# Car.net
KiCad netlist of a schematic drawn in EAGLE
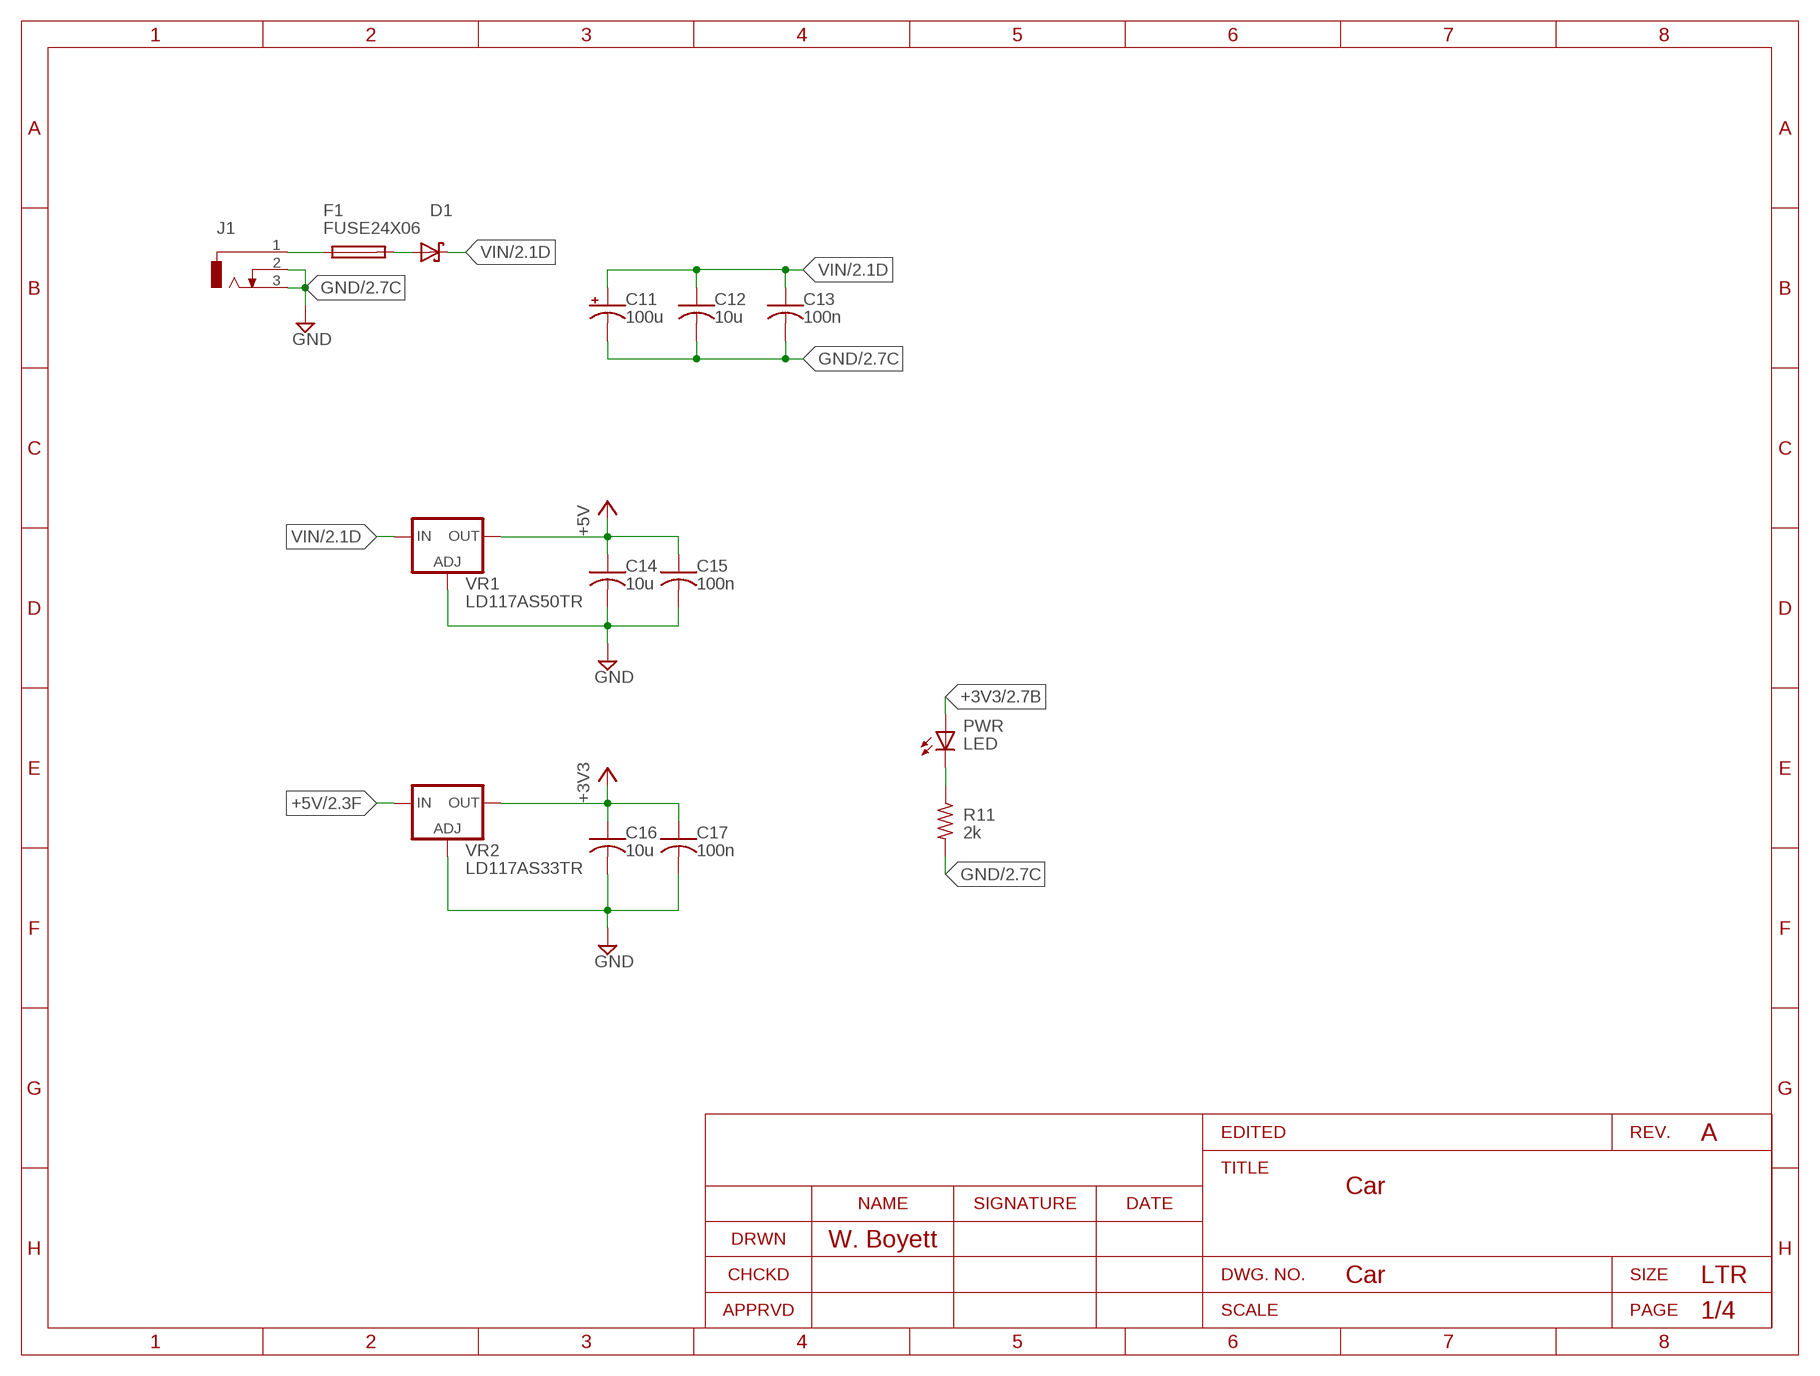
[diagram p0: schematic, sheet 1]
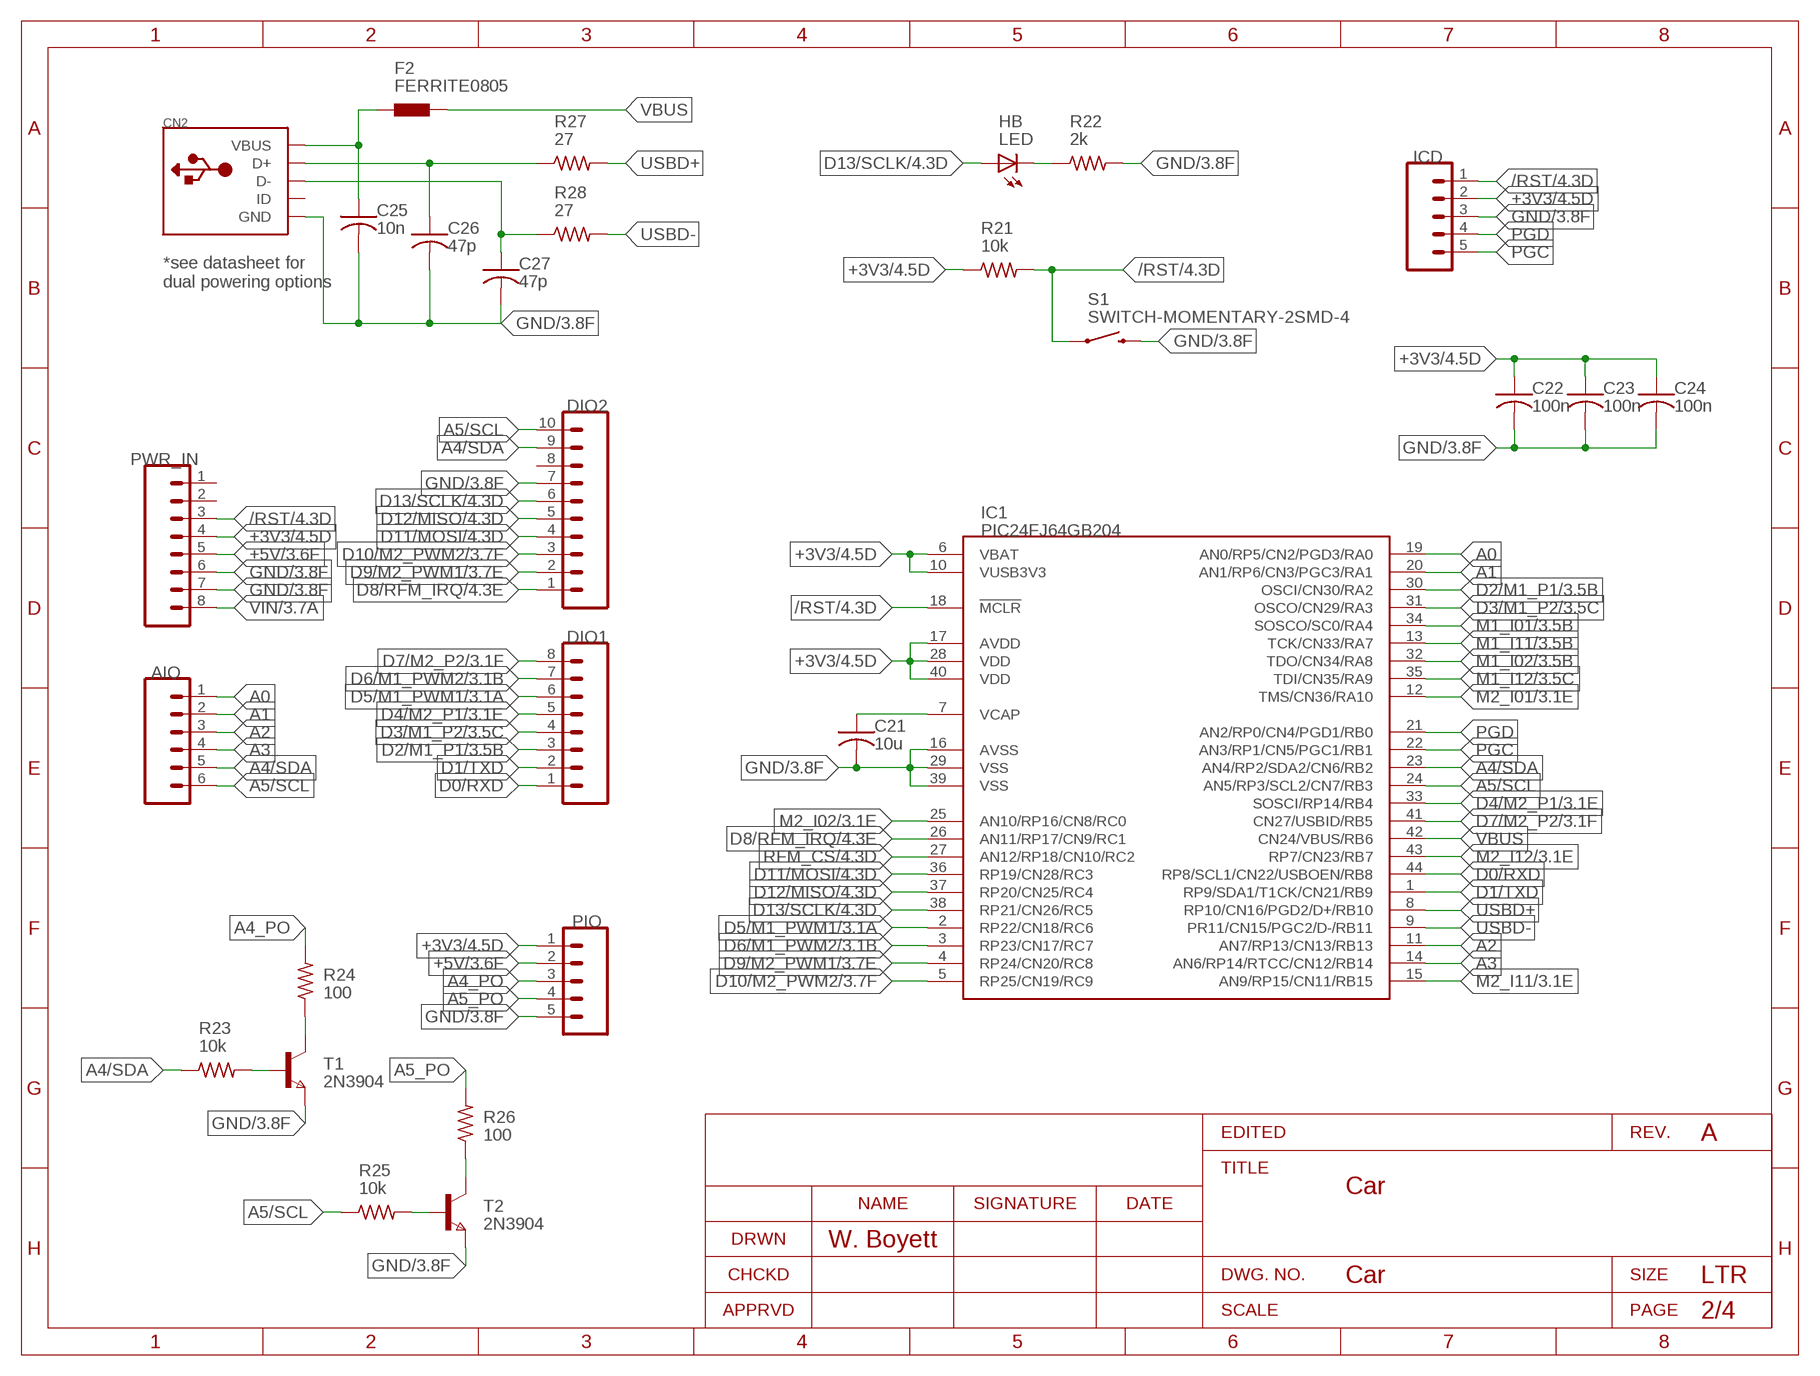
[diagram p1: schematic, sheet 2]
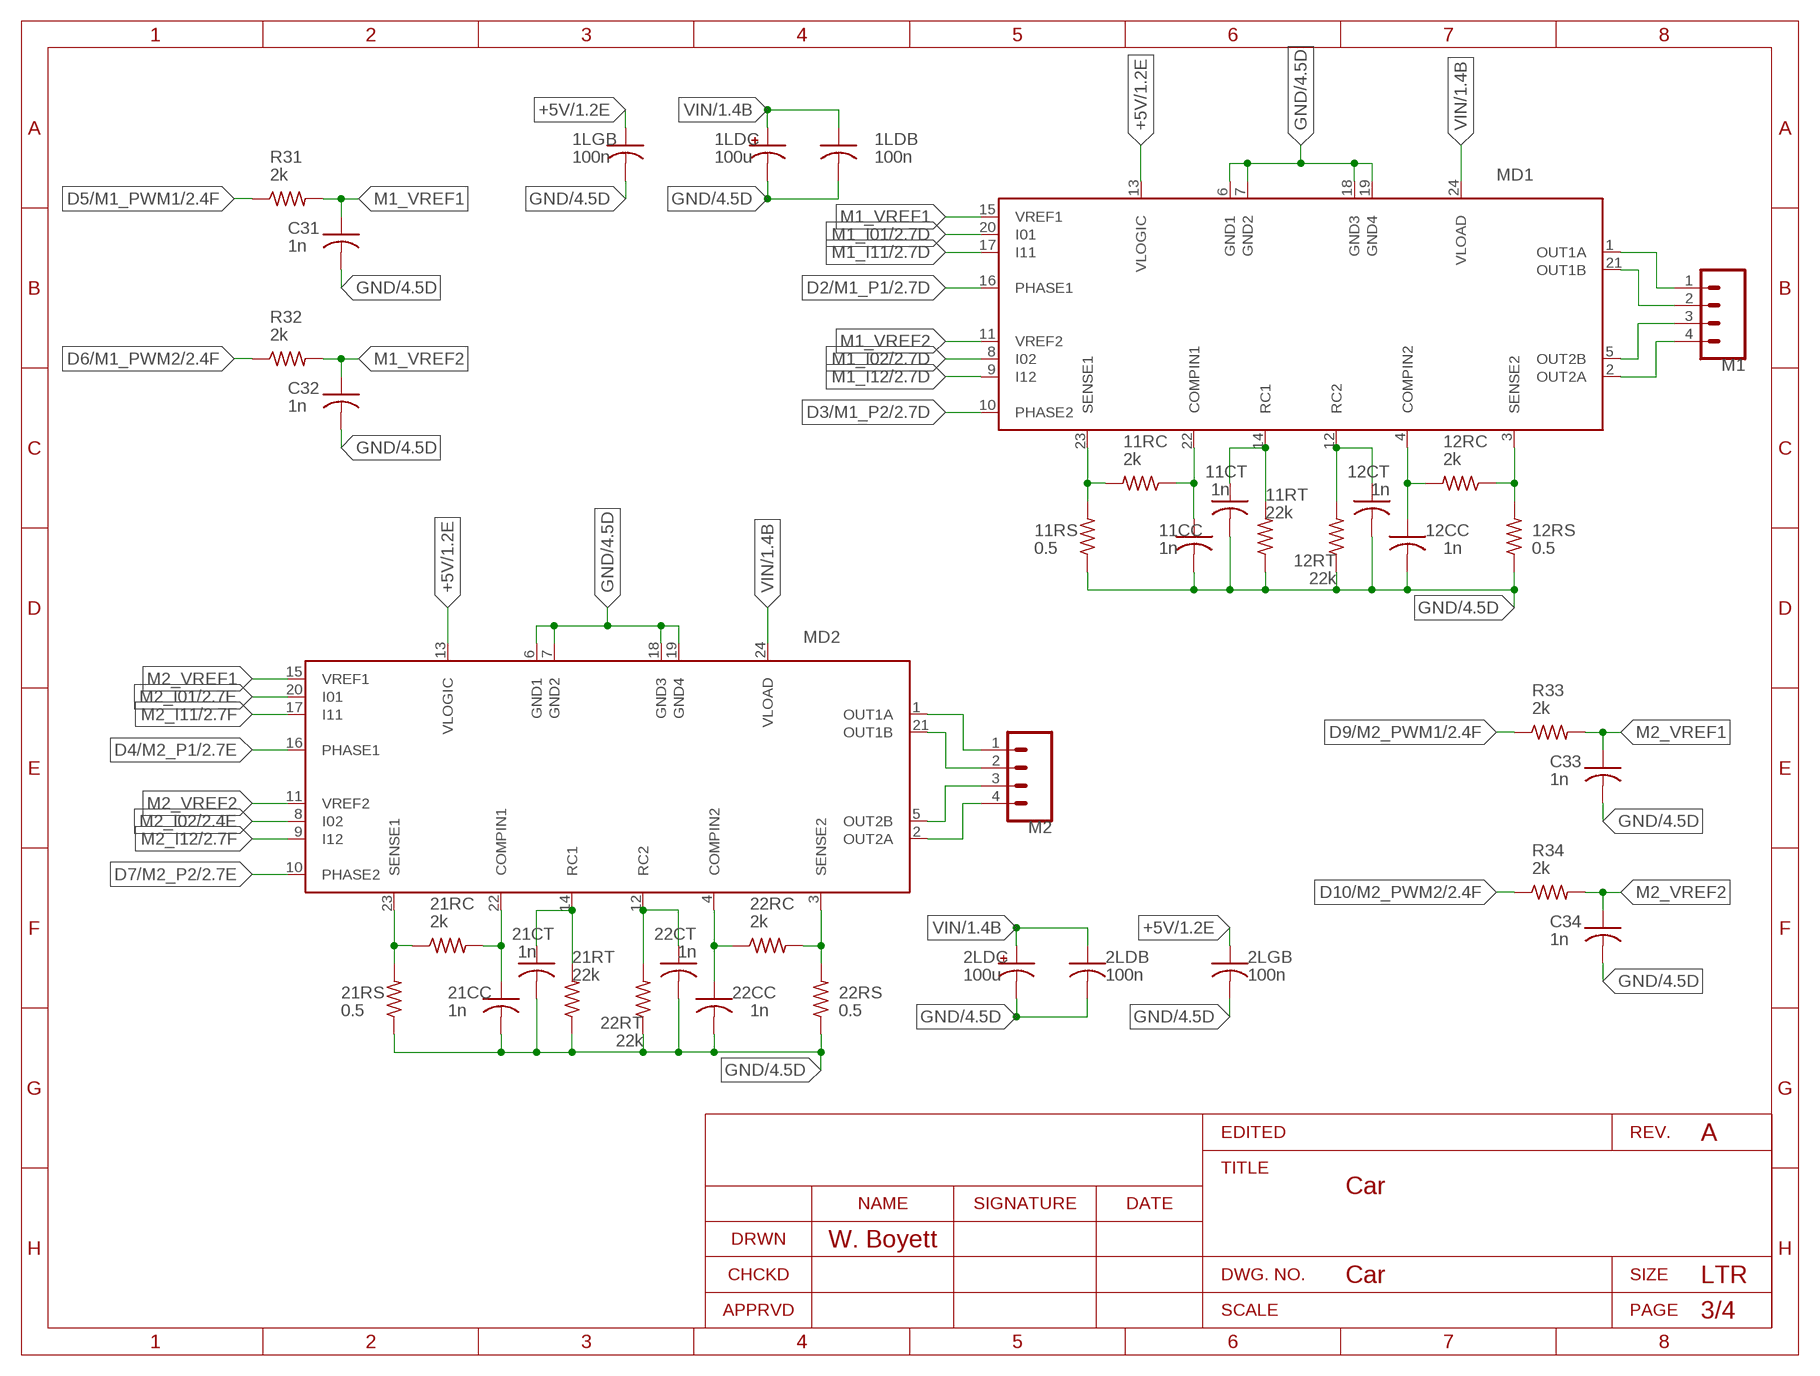
[diagram p2: schematic, sheet 3]
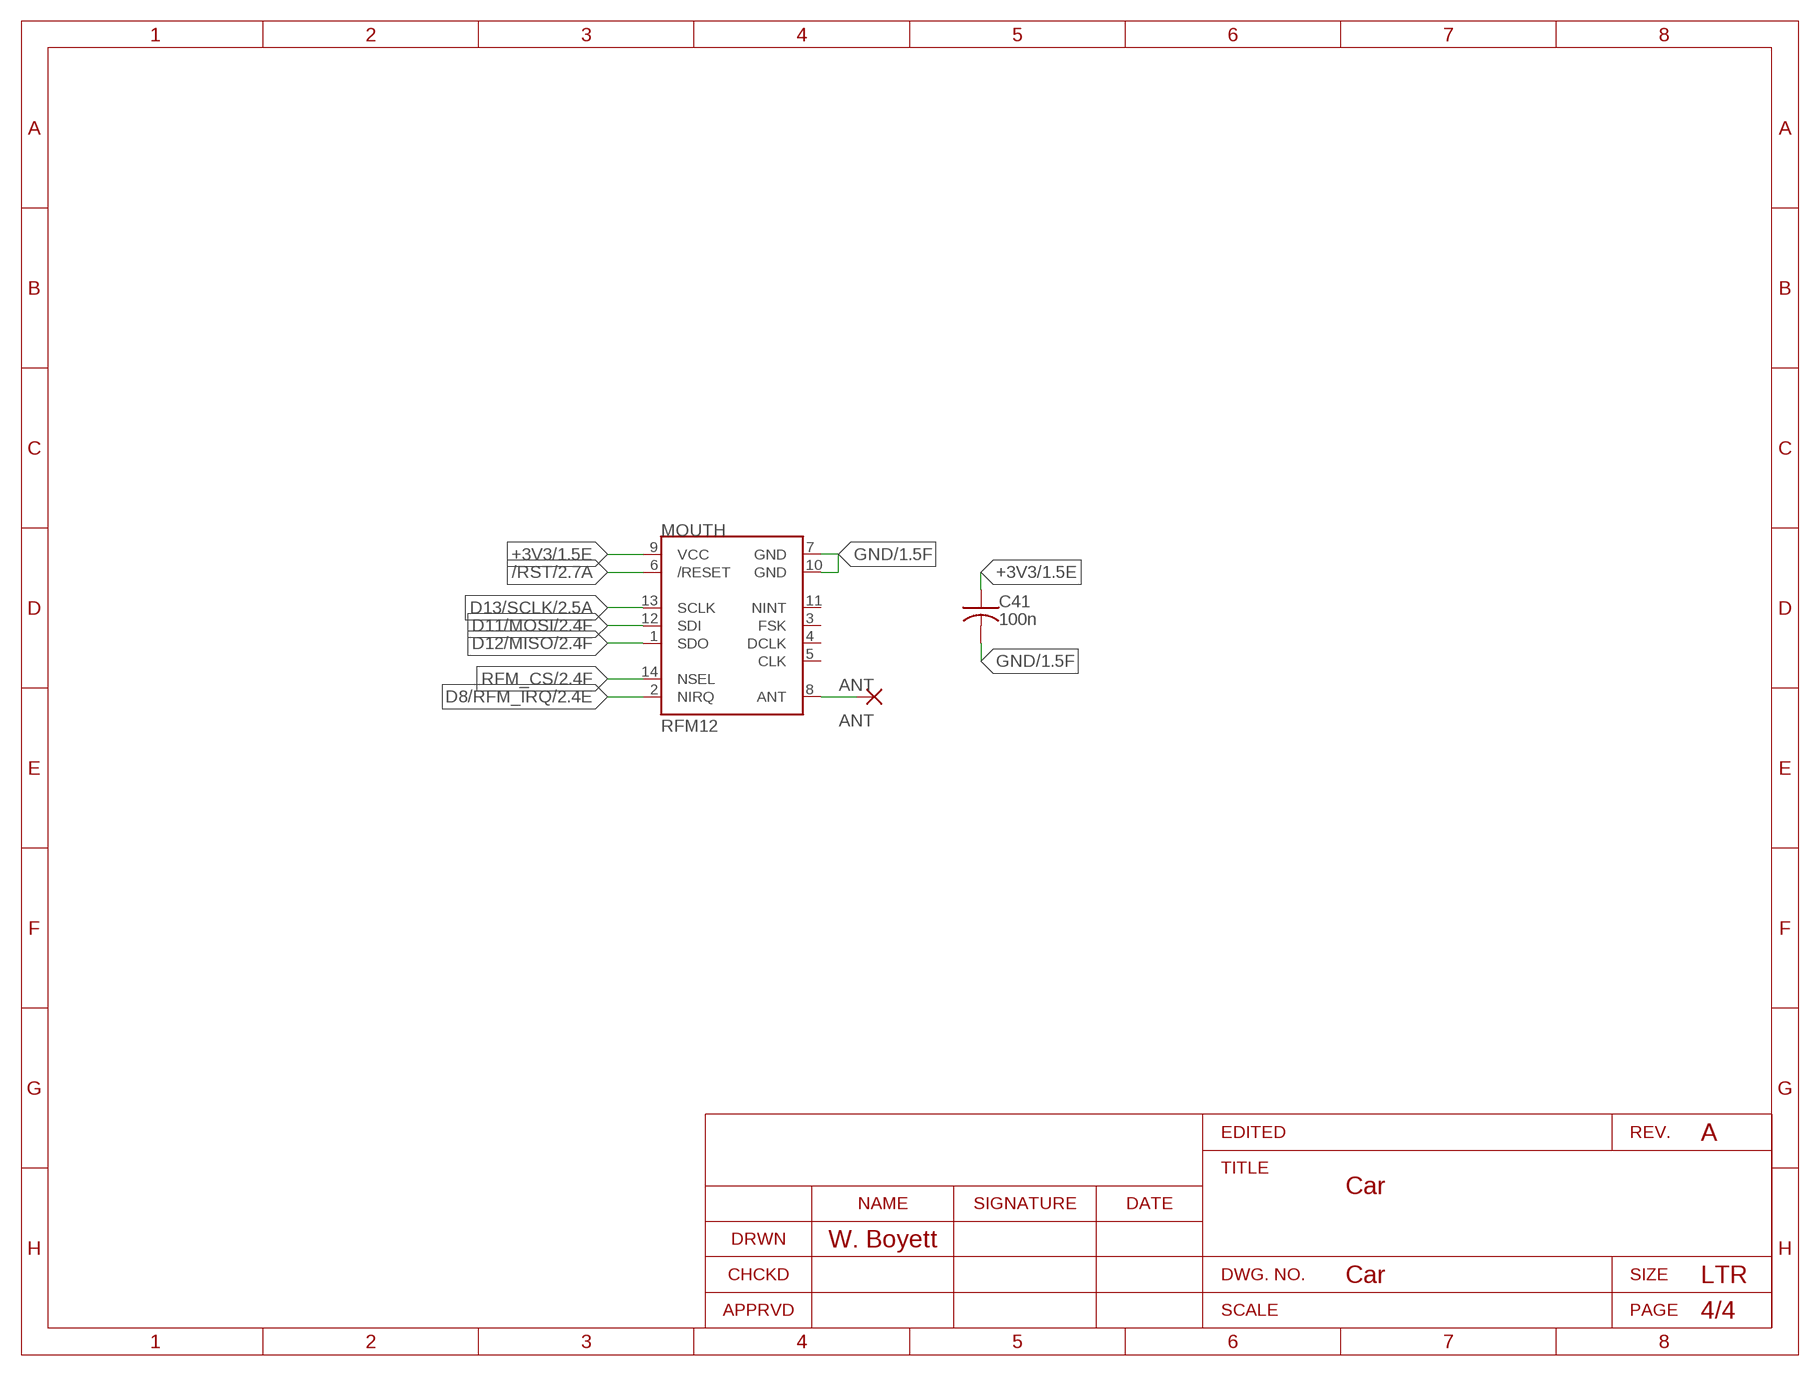
[diagram p3: schematic, sheet 4]

(export (version "E")
  (design (tool "Eeschema 10.0.6"))
  (components
    (comp (ref "C11")
      (value "100u")
      (footprint "eagle-import:PANASONIC_C")
      (libsource (lib "eagle-import") (part "CAP_POLC"))
    )
    (comp (ref "C12")
      (value "10u")
      (footprint "eagle-import:C1206")
      (libsource (lib "eagle-import") (part "C-USC1206"))
    )
    (comp (ref "C13")
      (value "100n")
      (footprint "eagle-import:C0805")
      (libsource (lib "eagle-import") (part "C-USC0805"))
    )
    (comp (ref "C14")
      (value "10u")
      (footprint "eagle-import:C1206")
      (libsource (lib "eagle-import") (part "C-USC1206"))
    )
    (comp (ref "C15")
      (value "100n")
      (footprint "eagle-import:C0805")
      (libsource (lib "eagle-import") (part "C-USC0805"))
    )
    (comp (ref "C16")
      (value "10u")
      (footprint "eagle-import:C1206")
      (libsource (lib "eagle-import") (part "C-USC1206"))
    )
    (comp (ref "C17")
      (value "100n")
      (footprint "eagle-import:C0805")
      (libsource (lib "eagle-import") (part "C-USC0805"))
    )
    (comp (ref "D1")
      (value "SCHOTTKY-DIODESMA")
      (footprint "eagle-import:SMA")
      (libsource (lib "eagle-import") (part "SCHOTTKY-DIODESMA"))
    )
    (comp (ref "F1")
      (value "FUSE24X06")
      (footprint "eagle-import:2SMD-24X06")
      (libsource (lib "eagle-import") (part "FUSE24X06"))
    )
    (comp (ref "J1")
      (value "DCJ0303")
      (footprint "eagle-import:DCJ0303")
      (libsource (lib "eagle-import") (part "DCJ0303"))
    )
    (comp (ref "PWR")
      (value "LED")
      (footprint "eagle-import:CHIP-LED0805")
      (libsource (lib "eagle-import") (part "LEDCHIP-LED0805"))
    )
    (comp (ref "R11")
      (value "2k")
      (footprint "eagle-import:R0805")
      (libsource (lib "eagle-import") (part "R-US_R0805"))
    )
    (comp (ref "VR1")
      (value "LD117AS50TR")
      (footprint "eagle-import:SOT223")
      (libsource (lib "eagle-import") (part "LD117A?S50TR"))
    )
    (comp (ref "VR2")
      (value "LD117AS33TR")
      (footprint "eagle-import:SOT223")
      (libsource (lib "eagle-import") (part "LD117A?S33TR"))
    )
    (comp (ref "1LDB")
      (value "100n")
      (footprint "eagle-import:C0805")
      (libsource (lib "eagle-import") (part "C-USC0805"))
    )
    (comp (ref "1LDC")
      (value "100u")
      (footprint "eagle-import:PANASONIC_C")
      (libsource (lib "eagle-import") (part "CAP_POLC"))
    )
    (comp (ref "1LGB")
      (value "100n")
      (footprint "eagle-import:C0805")
      (libsource (lib "eagle-import") (part "C-USC0805"))
    )
    (comp (ref "2LDB")
      (value "100n")
      (footprint "eagle-import:C0805")
      (libsource (lib "eagle-import") (part "C-USC0805"))
    )
    (comp (ref "2LDC")
      (value "100u")
      (footprint "eagle-import:PANASONIC_C")
      (libsource (lib "eagle-import") (part "CAP_POLC"))
    )
    (comp (ref "2LGB")
      (value "100n")
      (footprint "eagle-import:C0805")
      (libsource (lib "eagle-import") (part "C-USC0805"))
    )
    (comp (ref "11CC")
      (value "1n")
      (footprint "eagle-import:C0805")
      (libsource (lib "eagle-import") (part "C-USC0805"))
    )
    (comp (ref "11CT")
      (value "1n")
      (footprint "eagle-import:C0805")
      (libsource (lib "eagle-import") (part "C-USC0805"))
    )
    (comp (ref "11RC")
      (value "2k")
      (footprint "eagle-import:R0805")
      (libsource (lib "eagle-import") (part "R-US_R0805"))
    )
    (comp (ref "11RS")
      (value "0.5")
      (footprint "eagle-import:R1210")
      (libsource (lib "eagle-import") (part "resistor_R-US_R1210"))
    )
    (comp (ref "11RT")
      (value "22k")
      (footprint "eagle-import:R0805")
      (libsource (lib "eagle-import") (part "R-US_R0805"))
    )
    (comp (ref "12CC")
      (value "1n")
      (footprint "eagle-import:C0805")
      (libsource (lib "eagle-import") (part "C-USC0805"))
    )
    (comp (ref "12CT")
      (value "1n")
      (footprint "eagle-import:C0805")
      (libsource (lib "eagle-import") (part "C-USC0805"))
    )
    (comp (ref "12RC")
      (value "2k")
      (footprint "eagle-import:R0805")
      (libsource (lib "eagle-import") (part "R-US_R0805"))
    )
    (comp (ref "12RS")
      (value "0.5")
      (footprint "eagle-import:R1210")
      (libsource (lib "eagle-import") (part "resistor_R-US_R1210"))
    )
    (comp (ref "12RT")
      (value "22k")
      (footprint "eagle-import:R0805")
      (libsource (lib "eagle-import") (part "R-US_R0805"))
    )
    (comp (ref "21CC")
      (value "1n")
      (footprint "eagle-import:C0805")
      (libsource (lib "eagle-import") (part "C-USC0805"))
    )
    (comp (ref "21CT")
      (value "1n")
      (footprint "eagle-import:C0805")
      (libsource (lib "eagle-import") (part "C-USC0805"))
    )
    (comp (ref "21RC")
      (value "2k")
      (footprint "eagle-import:R0805")
      (libsource (lib "eagle-import") (part "R-US_R0805"))
    )
    (comp (ref "21RS")
      (value "0.5")
      (footprint "eagle-import:R1210")
      (libsource (lib "eagle-import") (part "resistor_R-US_R1210"))
    )
    (comp (ref "21RT")
      (value "22k")
      (footprint "eagle-import:R0805")
      (libsource (lib "eagle-import") (part "R-US_R0805"))
    )
    (comp (ref "22CC")
      (value "1n")
      (footprint "eagle-import:C0805")
      (libsource (lib "eagle-import") (part "C-USC0805"))
    )
    (comp (ref "22CT")
      (value "1n")
      (footprint "eagle-import:C0805")
      (libsource (lib "eagle-import") (part "C-USC0805"))
    )
    (comp (ref "22RC")
      (value "2k")
      (footprint "eagle-import:R0805")
      (libsource (lib "eagle-import") (part "R-US_R0805"))
    )
    (comp (ref "22RS")
      (value "0.5")
      (footprint "eagle-import:R1210")
      (libsource (lib "eagle-import") (part "resistor_R-US_R1210"))
    )
    (comp (ref "22RT")
      (value "22k")
      (footprint "eagle-import:R0805")
      (libsource (lib "eagle-import") (part "R-US_R0805"))
    )
    (comp (ref "C31")
      (value "1n")
      (footprint "eagle-import:C0805")
      (libsource (lib "eagle-import") (part "C-USC0805"))
    )
    (comp (ref "C32")
      (value "1n")
      (footprint "eagle-import:C0805")
      (libsource (lib "eagle-import") (part "C-USC0805"))
    )
    (comp (ref "C33")
      (value "1n")
      (footprint "eagle-import:C0805")
      (libsource (lib "eagle-import") (part "C-USC0805"))
    )
    (comp (ref "C34")
      (value "1n")
      (footprint "eagle-import:C0805")
      (libsource (lib "eagle-import") (part "C-USC0805"))
    )
    (comp (ref "M1")
      (value "M04LOCK")
      (footprint "eagle-import:1X04_LOCK")
      (libsource (lib "eagle-import") (part "M04LOCK"))
    )
    (comp (ref "M2")
      (value "M04LOCK")
      (footprint "eagle-import:1X04_LOCK")
      (libsource (lib "eagle-import") (part "M04LOCK"))
    )
    (comp (ref "MD1")
      (value "MTS62C19A")
      (footprint "eagle-import:SOP24L")
      (libsource (lib "eagle-import") (part "MTS62C19A"))
    )
    (comp (ref "MD2")
      (value "MTS62C19A")
      (footprint "eagle-import:SOP24L")
      (libsource (lib "eagle-import") (part "MTS62C19A"))
    )
    (comp (ref "R31")
      (value "2k")
      (footprint "eagle-import:R0805")
      (libsource (lib "eagle-import") (part "R-US_R0805"))
    )
    (comp (ref "R32")
      (value "2k")
      (footprint "eagle-import:R0805")
      (libsource (lib "eagle-import") (part "R-US_R0805"))
    )
    (comp (ref "R33")
      (value "2k")
      (footprint "eagle-import:R0805")
      (libsource (lib "eagle-import") (part "R-US_R0805"))
    )
    (comp (ref "R34")
      (value "2k")
      (footprint "eagle-import:R0805")
      (libsource (lib "eagle-import") (part "R-US_R0805"))
    )
    (comp (ref "AIO")
      (value "M06LOCK")
      (footprint "eagle-import:1X06_LOCK")
      (libsource (lib "eagle-import") (part "M06LOCK"))
    )
    (comp (ref "C21")
      (value "10u")
      (footprint "eagle-import:C1206")
      (libsource (lib "eagle-import") (part "C-USC1206"))
    )
    (comp (ref "C22")
      (value "100n")
      (footprint "eagle-import:C0805")
      (libsource (lib "eagle-import") (part "C-USC0805"))
    )
    (comp (ref "C23")
      (value "100n")
      (footprint "eagle-import:C0805")
      (libsource (lib "eagle-import") (part "C-USC0805"))
    )
    (comp (ref "C24")
      (value "100n")
      (footprint "eagle-import:C0805")
      (libsource (lib "eagle-import") (part "C-USC0805"))
    )
    (comp (ref "C25")
      (value "10n")
      (footprint "eagle-import:C0805")
      (fields (field (name "PN-DK") "399-1158-1-ND"))
      (libsource (lib "eagle-import") (part "C-USC0805"))
    )
    (comp (ref "C26")
      (value "47p")
      (footprint "eagle-import:C0805")
      (fields (field (name "PN-DK") "399-1117-1-ND"))
      (libsource (lib "eagle-import") (part "C-USC0805"))
    )
    (comp (ref "C27")
      (value "47p")
      (footprint "eagle-import:C0805")
      (fields (field (name "PN-DK") "399-1117-1-ND"))
      (libsource (lib "eagle-import") (part "C-USC0805"))
    )
    (comp (ref "CN2")
      (value "USBMINIB")
      (footprint "eagle-import:USB-MINIB")
      (libsource (lib "eagle-import") (part "USBMINIB"))
    )
    (comp (ref "DIO1")
      (value "M08LOCK")
      (footprint "eagle-import:1X08_LOCK")
      (libsource (lib "eagle-import") (part "M08LOCK"))
    )
    (comp (ref "DIO2")
      (value "M10LOCK")
      (footprint "eagle-import:1X10_LOCK")
      (libsource (lib "eagle-import") (part "M10LOCK"))
    )
    (comp (ref "F2")
      (value "FERRITE0805")
      (footprint "eagle-import:0805")
      (libsource (lib "eagle-import") (part "FERRITE0805"))
    )
    (comp (ref "HB")
      (value "LED")
      (footprint "eagle-import:CHIP-LED0805")
      (libsource (lib "eagle-import") (part "LEDCHIP-LED0805"))
    )
    (comp (ref "IC1")
      (value "PIC24FJ64GB204")
      (footprint "eagle-import:TQFP44")
      (fields (field (name "MPN") "PIC24FJ64GA004-E/PT"))
      (libsource (lib "eagle-import") (part "PIC24FJ64GB204"))
    )
    (comp (ref "ICD")
      (value "M05LOCK")
      (footprint "eagle-import:1X05_LOCK")
      (libsource (lib "eagle-import") (part "M05LOCK"))
    )
    (comp (ref "PIO")
      (value "M05LOCK")
      (footprint "eagle-import:1X05_LOCK")
      (libsource (lib "eagle-import") (part "M05LOCK"))
    )
    (comp (ref "PWR_IN")
      (value "M08LOCK")
      (footprint "eagle-import:1X08_LOCK")
      (libsource (lib "eagle-import") (part "M08LOCK"))
    )
    (comp (ref "R21")
      (value "10k")
      (footprint "eagle-import:R0805")
      (libsource (lib "eagle-import") (part "R-US_R0805"))
    )
    (comp (ref "R22")
      (value "2k")
      (footprint "eagle-import:R0805")
      (libsource (lib "eagle-import") (part "R-US_R0805"))
    )
    (comp (ref "R23")
      (value "10k")
      (footprint "eagle-import:R0805")
      (libsource (lib "eagle-import") (part "R-US_R0805"))
    )
    (comp (ref "R24")
      (value "100")
      (footprint "eagle-import:R0805")
      (libsource (lib "eagle-import") (part "R-US_R0805"))
    )
    (comp (ref "R25")
      (value "10k")
      (footprint "eagle-import:R0805")
      (libsource (lib "eagle-import") (part "R-US_R0805"))
    )
    (comp (ref "R26")
      (value "100")
      (footprint "eagle-import:R0805")
      (libsource (lib "eagle-import") (part "R-US_R0805"))
    )
    (comp (ref "R27")
      (value "27")
      (footprint "eagle-import:R0805")
      (libsource (lib "eagle-import") (part "resistor_R-US_R0805"))
    )
    (comp (ref "R28")
      (value "27")
      (footprint "eagle-import:R0805")
      (libsource (lib "eagle-import") (part "resistor_R-US_R0805"))
    )
    (comp (ref "S1")
      (value "SWITCH-MOMENTARY-2SMD-4")
      (footprint "eagle-import:TACTILE_SWITCH_TALL")
      (libsource (lib "eagle-import") (part "SWITCH-MOMENTARY-2SMD-4"))
    )
    (comp (ref "T1")
      (value "2N3904")
      (footprint "eagle-import:SOT-23")
      (fields (field (name "MPN") "DSS20201L-7"))
      (libsource (lib "eagle-import") (part "NPNSOT23"))
    )
    (comp (ref "T2")
      (value "2N3904")
      (footprint "eagle-import:SOT-23")
      (fields (field (name "MPN") "DSS20201L-7"))
      (libsource (lib "eagle-import") (part "NPNSOT23"))
    )
    (comp (ref "ANT")
      (value "ANT")
      (footprint "eagle-import:2,15_1,0")
      (libsource (lib "eagle-import") (part "2,15/1,0"))
    )
    (comp (ref "C41")
      (value "100n")
      (footprint "eagle-import:C0805")
      (libsource (lib "eagle-import") (part "C-USC0805"))
    )
    (comp (ref "MOUTH")
      (value "RFM12")
      (footprint "eagle-import:RFM12-XXX-S2")
      (libsource (lib "eagle-import") (part "RFM12"))
    )
  )
  (nets
    (net (code "1") (name "+3V3") (class "Default")
      (node (ref "C16") (pin "1") (pinfunction "1_1") (pintype "passive"))
      (node (ref "C17") (pin "1") (pinfunction "1_1") (pintype "passive"))
      (node (ref "C22") (pin "1") (pinfunction "1_1") (pintype "passive"))
      (node (ref "C23") (pin "1") (pinfunction "1_1") (pintype "passive"))
      (node (ref "C24") (pin "1") (pinfunction "1_1") (pintype "passive"))
      (node (ref "C41") (pin "1") (pinfunction "1_1") (pintype "passive"))
      (node (ref "IC1") (pin "10") (pinfunction "VUSB3V3_10") (pintype "bidirectional"))
      (node (ref "IC1") (pin "17") (pinfunction "AVDD_17") (pintype "power_in"))
      (node (ref "IC1") (pin "28") (pinfunction "VDD_28") (pintype "power_in"))
      (node (ref "IC1") (pin "40") (pinfunction "VDD_40") (pintype "power_in"))
      (node (ref "IC1") (pin "6") (pinfunction "VBAT_6") (pintype "passive"))
      (node (ref "ICD") (pin "2") (pinfunction "2_2") (pintype "passive"))
      (node (ref "MOUTH") (pin "9") (pinfunction "VCC_9") (pintype "bidirectional"))
      (node (ref "PIO") (pin "1") (pinfunction "1_1") (pintype "passive"))
      (node (ref "PWR") (pin "A") (pinfunction "A_A") (pintype "passive"))
      (node (ref "PWR_IN") (pin "4") (pinfunction "4_4") (pintype "passive"))
      (node (ref "R21") (pin "1") (pinfunction "1_1") (pintype "passive"))
      (node (ref "VR2") (pin "2") (pinfunction "OUT_2") (pintype "passive"))
      (node (ref "VR2") (pin "4") (pinfunction "OUT_4") (pintype "passive"))
    )
    (net (code "2") (name "+5V") (class "Default")
      (node (ref "1LGB") (pin "1") (pinfunction "1_1") (pintype "passive"))
      (node (ref "2LGB") (pin "1") (pinfunction "1_1") (pintype "passive"))
      (node (ref "C14") (pin "1") (pinfunction "1_1") (pintype "passive"))
      (node (ref "C15") (pin "1") (pinfunction "1_1") (pintype "passive"))
      (node (ref "MD1") (pin "13") (pinfunction "VLOGIC_13") (pintype "bidirectional"))
      (node (ref "MD2") (pin "13") (pinfunction "VLOGIC_13") (pintype "bidirectional"))
      (node (ref "PIO") (pin "2") (pinfunction "2_2") (pintype "passive"))
      (node (ref "PWR_IN") (pin "5") (pinfunction "5_5") (pintype "passive"))
      (node (ref "VR1") (pin "2") (pinfunction "OUT_2") (pintype "passive"))
      (node (ref "VR1") (pin "4") (pinfunction "OUT_4") (pintype "passive"))
      (node (ref "VR2") (pin "3") (pinfunction "IN_3") (pintype "input"))
    )
    (net (code "3") (name "A0") (class "Default")
      (node (ref "AIO") (pin "1") (pinfunction "1_1") (pintype "passive"))
      (node (ref "IC1") (pin "19") (pinfunction "AN0/RP5/CN2/PGD3/RA0_19") (pintype "bidirectional"))
    )
    (net (code "4") (name "A1") (class "Default")
      (node (ref "AIO") (pin "2") (pinfunction "2_2") (pintype "passive"))
      (node (ref "IC1") (pin "20") (pinfunction "AN1/RP6/CN3/PGC3/RA1_20") (pintype "bidirectional"))
    )
    (net (code "5") (name "A2") (class "Default")
      (node (ref "AIO") (pin "3") (pinfunction "3_3") (pintype "passive"))
      (node (ref "IC1") (pin "11") (pinfunction "AN7/RP13/CN13/RB13_11") (pintype "bidirectional"))
    )
    (net (code "6") (name "A3") (class "Default")
      (node (ref "AIO") (pin "4") (pinfunction "4_4") (pintype "passive"))
      (node (ref "IC1") (pin "14") (pinfunction "AN6/RP14/RTCC/CN12/RB14_14") (pintype "bidirectional"))
    )
    (net (code "7") (name "A4_PO") (class "Default")
      (node (ref "PIO") (pin "3") (pinfunction "3_3") (pintype "passive"))
      (node (ref "R24") (pin "2") (pinfunction "2_2") (pintype "passive"))
    )
    (net (code "8") (name "A4{slash}SDA") (class "Default")
      (node (ref "AIO") (pin "5") (pinfunction "5_5") (pintype "passive"))
      (node (ref "DIO2") (pin "9") (pinfunction "9_9") (pintype "passive"))
      (node (ref "IC1") (pin "23") (pinfunction "AN4/RP2/SDA2/CN6/RB2_23") (pintype "bidirectional"))
      (node (ref "R23") (pin "1") (pinfunction "1_1") (pintype "passive"))
    )
    (net (code "9") (name "A5_PO") (class "Default")
      (node (ref "PIO") (pin "4") (pinfunction "4_4") (pintype "passive"))
      (node (ref "R26") (pin "2") (pinfunction "2_2") (pintype "passive"))
    )
    (net (code "10") (name "A5{slash}SCL") (class "Default")
      (node (ref "AIO") (pin "6") (pinfunction "6_6") (pintype "passive"))
      (node (ref "DIO2") (pin "10") (pinfunction "10_10") (pintype "passive"))
      (node (ref "IC1") (pin "24") (pinfunction "AN5/RP3/SCL2/CN7/RB3_24") (pintype "bidirectional"))
      (node (ref "R25") (pin "1") (pinfunction "1_1") (pintype "passive"))
    )
    (net (code "11") (name "D0{slash}RXD") (class "Default")
      (node (ref "DIO1") (pin "1") (pinfunction "1_1") (pintype "passive"))
      (node (ref "IC1") (pin "44") (pinfunction "RP8/SCL1/CN22/USBOEN/RB8_44") (pintype "bidirectional"))
    )
    (net (code "12") (name "D1{slash}TXD") (class "Default")
      (node (ref "DIO1") (pin "2") (pinfunction "2_2") (pintype "passive"))
      (node (ref "IC1") (pin "1") (pinfunction "RP9/SDA1/T1CK/CN21/RB9_1") (pintype "bidirectional"))
    )
    (net (code "13") (name "D2{slash}M1_P1") (class "Default")
      (node (ref "DIO1") (pin "3") (pinfunction "3_3") (pintype "passive"))
      (node (ref "IC1") (pin "30") (pinfunction "OSCI/CN30/RA2_30") (pintype "bidirectional"))
      (node (ref "MD1") (pin "16") (pinfunction "PHASE1_16") (pintype "bidirectional"))
    )
    (net (code "14") (name "D3{slash}M1_P2") (class "Default")
      (node (ref "DIO1") (pin "4") (pinfunction "4_4") (pintype "passive"))
      (node (ref "IC1") (pin "31") (pinfunction "OSCO/CN29/RA3_31") (pintype "bidirectional"))
      (node (ref "MD1") (pin "10") (pinfunction "PHASE2_10") (pintype "bidirectional"))
    )
    (net (code "15") (name "D4{slash}M2_P1") (class "Default")
      (node (ref "DIO1") (pin "5") (pinfunction "5_5") (pintype "passive"))
      (node (ref "IC1") (pin "33") (pinfunction "SOSCI/RP14/RB4_33") (pintype "bidirectional"))
      (node (ref "MD2") (pin "16") (pinfunction "PHASE1_16") (pintype "bidirectional"))
    )
    (net (code "16") (name "D5{slash}M1_PWM1") (class "Default")
      (node (ref "DIO1") (pin "6") (pinfunction "6_6") (pintype "passive"))
      (node (ref "IC1") (pin "2") (pinfunction "RP22/CN18/RC6_2") (pintype "bidirectional"))
      (node (ref "R31") (pin "1") (pinfunction "1_1") (pintype "passive"))
    )
    (net (code "17") (name "D6{slash}M1_PWM2") (class "Default")
      (node (ref "DIO1") (pin "7") (pinfunction "7_7") (pintype "passive"))
      (node (ref "IC1") (pin "3") (pinfunction "RP23/CN17/RC7_3") (pintype "bidirectional"))
      (node (ref "R32") (pin "1") (pinfunction "1_1") (pintype "passive"))
    )
    (net (code "18") (name "D7{slash}M2_P2") (class "Default")
      (node (ref "DIO1") (pin "8") (pinfunction "8_8") (pintype "passive"))
      (node (ref "IC1") (pin "41") (pinfunction "CN27/USBID/RB5_41") (pintype "bidirectional"))
      (node (ref "MD2") (pin "10") (pinfunction "PHASE2_10") (pintype "bidirectional"))
    )
    (net (code "19") (name "D8{slash}RFM_IRQ") (class "Default")
      (node (ref "DIO2") (pin "1") (pinfunction "1_1") (pintype "passive"))
      (node (ref "IC1") (pin "26") (pinfunction "AN11/RP17/CN9/RC1_26") (pintype "bidirectional"))
      (node (ref "MOUTH") (pin "2") (pinfunction "NIRQ_2") (pintype "output"))
    )
    (net (code "20") (name "D9{slash}M2_PWM1") (class "Default")
      (node (ref "DIO2") (pin "2") (pinfunction "2_2") (pintype "passive"))
      (node (ref "IC1") (pin "4") (pinfunction "RP24/CN20/RC8_4") (pintype "bidirectional"))
      (node (ref "R33") (pin "1") (pinfunction "1_1") (pintype "passive"))
    )
    (net (code "21") (name "D10{slash}M2_PWM2") (class "Default")
      (node (ref "DIO2") (pin "3") (pinfunction "3_3") (pintype "passive"))
      (node (ref "IC1") (pin "5") (pinfunction "RP25/CN19/RC9_5") (pintype "bidirectional"))
      (node (ref "R34") (pin "1") (pinfunction "1_1") (pintype "passive"))
    )
    (net (code "22") (name "D11{slash}MOSI") (class "Default")
      (node (ref "DIO2") (pin "4") (pinfunction "4_4") (pintype "passive"))
      (node (ref "IC1") (pin "36") (pinfunction "RP19/CN28/RC3_36") (pintype "bidirectional"))
      (node (ref "MOUTH") (pin "12") (pinfunction "SDI_12") (pintype "input"))
    )
    (net (code "23") (name "D12{slash}MISO") (class "Default")
      (node (ref "DIO2") (pin "5") (pinfunction "5_5") (pintype "passive"))
      (node (ref "IC1") (pin "37") (pinfunction "RP20/CN25/RC4_37") (pintype "bidirectional"))
      (node (ref "MOUTH") (pin "1") (pinfunction "SDO_1") (pintype "output"))
    )
    (net (code "24") (name "D13{slash}SCLK") (class "Default")
      (node (ref "DIO2") (pin "6") (pinfunction "6_6") (pintype "passive"))
      (node (ref "HB") (pin "A") (pinfunction "A_A") (pintype "passive"))
      (node (ref "IC1") (pin "38") (pinfunction "RP21/CN26/RC5_38") (pintype "bidirectional"))
      (node (ref "MOUTH") (pin "13") (pinfunction "SCLK_13") (pintype "input"))
    )
    (net (code "25") (name "GND") (class "Default")
      (node (ref "11CC") (pin "2") (pinfunction "2_2") (pintype "passive"))
      (node (ref "11CT") (pin "2") (pinfunction "2_2") (pintype "passive"))
      (node (ref "11RS") (pin "1") (pinfunction "1_1") (pintype "passive"))
      (node (ref "11RT") (pin "1") (pinfunction "1_1") (pintype "passive"))
      (node (ref "12CC") (pin "2") (pinfunction "2_2") (pintype "passive"))
      (node (ref "12CT") (pin "2") (pinfunction "2_2") (pintype "passive"))
      (node (ref "12RS") (pin "1") (pinfunction "1_1") (pintype "passive"))
      (node (ref "12RT") (pin "1") (pinfunction "1_1") (pintype "passive"))
      (node (ref "1LDB") (pin "2") (pinfunction "2_2") (pintype "passive"))
      (node (ref "1LDC") (pin "-") (pinfunction "-_-") (pintype "passive"))
      (node (ref "1LGB") (pin "2") (pinfunction "2_2") (pintype "passive"))
      (node (ref "21CC") (pin "2") (pinfunction "2_2") (pintype "passive"))
      (node (ref "21CT") (pin "2") (pinfunction "2_2") (pintype "passive"))
      (node (ref "21RS") (pin "1") (pinfunction "1_1") (pintype "passive"))
      (node (ref "21RT") (pin "1") (pinfunction "1_1") (pintype "passive"))
      (node (ref "22CC") (pin "2") (pinfunction "2_2") (pintype "passive"))
      (node (ref "22CT") (pin "2") (pinfunction "2_2") (pintype "passive"))
      (node (ref "22RS") (pin "1") (pinfunction "1_1") (pintype "passive"))
      (node (ref "22RT") (pin "1") (pinfunction "1_1") (pintype "passive"))
      (node (ref "2LDB") (pin "2") (pinfunction "2_2") (pintype "passive"))
      (node (ref "2LDC") (pin "-") (pinfunction "-_-") (pintype "passive"))
      (node (ref "2LGB") (pin "2") (pinfunction "2_2") (pintype "passive"))
      (node (ref "C11") (pin "-") (pinfunction "-_-") (pintype "passive"))
      (node (ref "C12") (pin "2") (pinfunction "2_2") (pintype "passive"))
      (node (ref "C13") (pin "2") (pinfunction "2_2") (pintype "passive"))
      (node (ref "C14") (pin "2") (pinfunction "2_2") (pintype "passive"))
      (node (ref "C15") (pin "2") (pinfunction "2_2") (pintype "passive"))
      (node (ref "C16") (pin "2") (pinfunction "2_2") (pintype "passive"))
      (node (ref "C17") (pin "2") (pinfunction "2_2") (pintype "passive"))
      (node (ref "C21") (pin "2") (pinfunction "2_2") (pintype "passive"))
      (node (ref "C22") (pin "2") (pinfunction "2_2") (pintype "passive"))
      (node (ref "C23") (pin "2") (pinfunction "2_2") (pintype "passive"))
      (node (ref "C24") (pin "2") (pinfunction "2_2") (pintype "passive"))
      (node (ref "C25") (pin "2") (pinfunction "2_2") (pintype "passive"))
      (node (ref "C26") (pin "2") (pinfunction "2_2") (pintype "passive"))
      (node (ref "C27") (pin "2") (pinfunction "2_2") (pintype "passive"))
      (node (ref "C31") (pin "2") (pinfunction "2_2") (pintype "passive"))
      (node (ref "C32") (pin "2") (pinfunction "2_2") (pintype "passive"))
      (node (ref "C33") (pin "2") (pinfunction "2_2") (pintype "passive"))
      (node (ref "C34") (pin "2") (pinfunction "2_2") (pintype "passive"))
      (node (ref "C41") (pin "2") (pinfunction "2_2") (pintype "passive"))
      (node (ref "CN2") (pin "GND") (pinfunction "GND_GND") (pintype "power_in"))
      (node (ref "DIO2") (pin "7") (pinfunction "7_7") (pintype "passive"))
      (node (ref "IC1") (pin "16") (pinfunction "AVSS_16") (pintype "power_in"))
      (node (ref "IC1") (pin "29") (pinfunction "VSS_29") (pintype "power_in"))
      (node (ref "IC1") (pin "39") (pinfunction "VSS_39") (pintype "power_in"))
      (node (ref "ICD") (pin "3") (pinfunction "3_3") (pintype "passive"))
      (node (ref "J1") (pin "2") (pinfunction "2_2") (pintype "passive"))
      (node (ref "J1") (pin "3") (pinfunction "3_3") (pintype "passive"))
      (node (ref "MD1") (pin "18") (pinfunction "GND3_18") (pintype "bidirectional"))
      (node (ref "MD1") (pin "19") (pinfunction "GND4_19") (pintype "bidirectional"))
      (node (ref "MD1") (pin "6") (pinfunction "GND1_6") (pintype "bidirectional"))
      (node (ref "MD1") (pin "7") (pinfunction "GND2_7") (pintype "bidirectional"))
      (node (ref "MD2") (pin "18") (pinfunction "GND3_18") (pintype "bidirectional"))
      (node (ref "MD2") (pin "19") (pinfunction "GND4_19") (pintype "bidirectional"))
      (node (ref "MD2") (pin "6") (pinfunction "GND1_6") (pintype "bidirectional"))
      (node (ref "MD2") (pin "7") (pinfunction "GND2_7") (pintype "bidirectional"))
      (node (ref "MOUTH") (pin "10") (pinfunction "GND_10") (pintype "bidirectional"))
      (node (ref "MOUTH") (pin "7") (pinfunction "GND_7") (pintype "bidirectional"))
      (node (ref "PIO") (pin "5") (pinfunction "5_5") (pintype "passive"))
      (node (ref "PWR_IN") (pin "6") (pinfunction "6_6") (pintype "passive"))
      (node (ref "PWR_IN") (pin "7") (pinfunction "7_7") (pintype "passive"))
      (node (ref "R11") (pin "2") (pinfunction "2_2") (pintype "passive"))
      (node (ref "R22") (pin "2") (pinfunction "2_2") (pintype "passive"))
      (node (ref "S1") (pin "B2") (pinfunction "2_B2") (pintype "passive"))
      (node (ref "T1") (pin "2") (pinfunction "E_2") (pintype "passive"))
      (node (ref "T2") (pin "2") (pinfunction "E_2") (pintype "passive"))
      (node (ref "VR1") (pin "1") (pinfunction "ADJ_1") (pintype "input"))
      (node (ref "VR2") (pin "1") (pinfunction "ADJ_1") (pintype "input"))
    )
    (net (code "26") (name "M1_I01") (class "Default")
      (node (ref "IC1") (pin "34") (pinfunction "SOSCO/SC0/RA4_34") (pintype "bidirectional"))
      (node (ref "MD1") (pin "20") (pinfunction "I01_20") (pintype "bidirectional"))
    )
    (net (code "27") (name "M1_I02") (class "Default")
      (node (ref "IC1") (pin "32") (pinfunction "TDO/CN34/RA8_32") (pintype "output"))
      (node (ref "MD1") (pin "8") (pinfunction "I02_8") (pintype "bidirectional"))
    )
    (net (code "28") (name "M1_I11") (class "Default")
      (node (ref "IC1") (pin "13") (pinfunction "TCK/CN33/RA7_13") (pintype "input"))
      (node (ref "MD1") (pin "17") (pinfunction "I11_17") (pintype "bidirectional"))
    )
    (net (code "29") (name "M1_I12") (class "Default")
      (node (ref "IC1") (pin "35") (pinfunction "TDI/CN35/RA9_35") (pintype "input"))
      (node (ref "MD1") (pin "9") (pinfunction "I12_9") (pintype "bidirectional"))
    )
    (net (code "30") (name "M1_VREF1") (class "Default")
      (node (ref "C31") (pin "1") (pinfunction "1_1") (pintype "passive"))
      (node (ref "MD1") (pin "15") (pinfunction "VREF1_15") (pintype "bidirectional"))
      (node (ref "R31") (pin "2") (pinfunction "2_2") (pintype "passive"))
    )
    (net (code "31") (name "M1_VREF2") (class "Default")
      (node (ref "C32") (pin "1") (pinfunction "1_1") (pintype "passive"))
      (node (ref "MD1") (pin "11") (pinfunction "VREF2_11") (pintype "bidirectional"))
      (node (ref "R32") (pin "2") (pinfunction "2_2") (pintype "passive"))
    )
    (net (code "32") (name "M2_I01") (class "Default")
      (node (ref "IC1") (pin "12") (pinfunction "TMS/CN36/RA10_12") (pintype "input"))
      (node (ref "MD2") (pin "20") (pinfunction "I01_20") (pintype "bidirectional"))
    )
    (net (code "33") (name "M2_I02") (class "Default")
      (node (ref "IC1") (pin "25") (pinfunction "AN10/RP16/CN8/RC0_25") (pintype "bidirectional"))
      (node (ref "MD2") (pin "8") (pinfunction "I02_8") (pintype "bidirectional"))
    )
    (net (code "34") (name "M2_I11") (class "Default")
      (node (ref "IC1") (pin "15") (pinfunction "AN9/RP15/CN11/RB15_15") (pintype "bidirectional"))
      (node (ref "MD2") (pin "17") (pinfunction "I11_17") (pintype "bidirectional"))
    )
    (net (code "35") (name "M2_I12") (class "Default")
      (node (ref "IC1") (pin "43") (pinfunction "RP7/CN23/RB7_43") (pintype "bidirectional"))
      (node (ref "MD2") (pin "9") (pinfunction "I12_9") (pintype "bidirectional"))
    )
    (net (code "36") (name "M2_VREF1") (class "Default")
      (node (ref "C33") (pin "1") (pinfunction "1_1") (pintype "passive"))
      (node (ref "MD2") (pin "15") (pinfunction "VREF1_15") (pintype "bidirectional"))
      (node (ref "R33") (pin "2") (pinfunction "2_2") (pintype "passive"))
    )
    (net (code "37") (name "M2_VREF2") (class "Default")
      (node (ref "C34") (pin "1") (pinfunction "1_1") (pintype "passive"))
      (node (ref "MD2") (pin "11") (pinfunction "VREF2_11") (pintype "bidirectional"))
      (node (ref "R34") (pin "2") (pinfunction "2_2") (pintype "passive"))
    )
    (net (code "38") (name "Net-(ANT-P)") (class "Default")
      (node (ref "ANT") (pin "1") (pinfunction "P_1") (pintype "passive"))
      (node (ref "MOUTH") (pin "8") (pinfunction "ANT_8") (pintype "bidirectional"))
    )
    (net (code "39") (name "Net-(C25-Pad1)") (class "Default")
      (node (ref "C25") (pin "1") (pinfunction "1_1") (pintype "passive"))
      (node (ref "CN2") (pin "VBUS") (pinfunction "VBUS_VBUS") (pintype "power_in"))
      (node (ref "F2") (pin "1") (pinfunction "1_1") (pintype "passive"))
    )
    (net (code "40") (name "Net-(C26-Pad1)") (class "Default")
      (node (ref "C26") (pin "1") (pinfunction "1_1") (pintype "passive"))
      (node (ref "CN2") (pin "D+") (pinfunction "D+_D+") (pintype "bidirectional"))
      (node (ref "R27") (pin "1") (pinfunction "1_1") (pintype "passive"))
    )
    (net (code "41") (name "Net-(C27-Pad1)") (class "Default")
      (node (ref "C27") (pin "1") (pinfunction "1_1") (pintype "passive"))
      (node (ref "CN2") (pin "D-") (pinfunction "D-_D-") (pintype "bidirectional"))
      (node (ref "R28") (pin "1") (pinfunction "1_1") (pintype "passive"))
    )
    (net (code "42") (name "Net-(F1-1)") (class "Default")
      (node (ref "F1") (pin "P$1") (pinfunction "1_P$1") (pintype "passive"))
      (node (ref "J1") (pin "1") (pinfunction "1_1") (pintype "passive"))
    )
    (net (code "43") (name "Net-(F1-2)") (class "Default")
      (node (ref "D1") (pin "A") (pinfunction "A_A") (pintype "passive"))
      (node (ref "F1") (pin "P$2") (pinfunction "2_P$2") (pintype "passive"))
    )
    (net (code "44") (name "Net-(HB-PadC)") (class "Default")
      (node (ref "HB") (pin "C") (pinfunction "C_C") (pintype "passive"))
      (node (ref "R22") (pin "1") (pinfunction "1_1") (pintype "passive"))
    )
    (net (code "45") (name "Net-(IC1-VCAP)") (class "Default")
      (node (ref "C21") (pin "1") (pinfunction "1_1") (pintype "passive"))
      (node (ref "IC1") (pin "7") (pinfunction "VCAP_7") (pintype "power_in"))
    )
    (net (code "46") (name "Net-(MD1-COMPIN1)") (class "Default")
      (node (ref "11CC") (pin "1") (pinfunction "1_1") (pintype "passive"))
      (node (ref "11RC") (pin "1") (pinfunction "1_1") (pintype "passive"))
      (node (ref "MD1") (pin "22") (pinfunction "COMPIN1_22") (pintype "bidirectional"))
    )
    (net (code "47") (name "Net-(MD1-COMPIN2)") (class "Default")
      (node (ref "12CC") (pin "1") (pinfunction "1_1") (pintype "passive"))
      (node (ref "12RC") (pin "2") (pinfunction "2_2") (pintype "passive"))
      (node (ref "MD1") (pin "4") (pinfunction "COMPIN2_4") (pintype "bidirectional"))
    )
    (net (code "48") (name "Net-(MD1-OUT1A)") (class "Default")
      (node (ref "M1") (pin "1") (pinfunction "1_1") (pintype "passive"))
      (node (ref "MD1") (pin "1") (pinfunction "OUT1A_1") (pintype "bidirectional"))
    )
    (net (code "49") (name "Net-(MD1-OUT1B)") (class "Default")
      (node (ref "M1") (pin "2") (pinfunction "2_2") (pintype "passive"))
      (node (ref "MD1") (pin "21") (pinfunction "OUT1B_21") (pintype "bidirectional"))
    )
    (net (code "50") (name "Net-(MD1-OUT2A)") (class "Default")
      (node (ref "M1") (pin "4") (pinfunction "4_4") (pintype "passive"))
      (node (ref "MD1") (pin "2") (pinfunction "OUT2A_2") (pintype "bidirectional"))
    )
    (net (code "51") (name "Net-(MD1-OUT2B)") (class "Default")
      (node (ref "M1") (pin "3") (pinfunction "3_3") (pintype "passive"))
      (node (ref "MD1") (pin "5") (pinfunction "OUT2B_5") (pintype "bidirectional"))
    )
    (net (code "52") (name "Net-(MD1-RC1)") (class "Default")
      (node (ref "11CT") (pin "1") (pinfunction "1_1") (pintype "passive"))
      (node (ref "11RT") (pin "2") (pinfunction "2_2") (pintype "passive"))
      (node (ref "MD1") (pin "14") (pinfunction "RC1_14") (pintype "bidirectional"))
    )
    (net (code "53") (name "Net-(MD1-RC2)") (class "Default")
      (node (ref "12CT") (pin "1") (pinfunction "1_1") (pintype "passive"))
      (node (ref "12RT") (pin "2") (pinfunction "2_2") (pintype "passive"))
      (node (ref "MD1") (pin "12") (pinfunction "RC2_12") (pintype "bidirectional"))
    )
    (net (code "54") (name "Net-(MD1-SENSE1)") (class "Default")
      (node (ref "11RC") (pin "2") (pinfunction "2_2") (pintype "passive"))
      (node (ref "11RS") (pin "2") (pinfunction "2_2") (pintype "passive"))
      (node (ref "MD1") (pin "23") (pinfunction "SENSE1_23") (pintype "bidirectional"))
    )
    (net (code "55") (name "Net-(MD1-SENSE2)") (class "Default")
      (node (ref "12RC") (pin "1") (pinfunction "1_1") (pintype "passive"))
      (node (ref "12RS") (pin "2") (pinfunction "2_2") (pintype "passive"))
      (node (ref "MD1") (pin "3") (pinfunction "SENSE2_3") (pintype "bidirectional"))
    )
    (net (code "56") (name "Net-(MD2-COMPIN1)") (class "Default")
      (node (ref "21CC") (pin "1") (pinfunction "1_1") (pintype "passive"))
      (node (ref "21RC") (pin "2") (pinfunction "2_2") (pintype "passive"))
      (node (ref "MD2") (pin "22") (pinfunction "COMPIN1_22") (pintype "bidirectional"))
    )
    (net (code "57") (name "Net-(MD2-COMPIN2)") (class "Default")
      (node (ref "22CC") (pin "1") (pinfunction "1_1") (pintype "passive"))
      (node (ref "22RC") (pin "1") (pinfunction "1_1") (pintype "passive"))
      (node (ref "MD2") (pin "4") (pinfunction "COMPIN2_4") (pintype "bidirectional"))
    )
    (net (code "58") (name "Net-(MD2-OUT1A)") (class "Default")
      (node (ref "M2") (pin "1") (pinfunction "1_1") (pintype "passive"))
      (node (ref "MD2") (pin "1") (pinfunction "OUT1A_1") (pintype "bidirectional"))
    )
    (net (code "59") (name "Net-(MD2-OUT1B)") (class "Default")
      (node (ref "M2") (pin "2") (pinfunction "2_2") (pintype "passive"))
      (node (ref "MD2") (pin "21") (pinfunction "OUT1B_21") (pintype "bidirectional"))
    )
    (net (code "60") (name "Net-(MD2-OUT2A)") (class "Default")
      (node (ref "M2") (pin "4") (pinfunction "4_4") (pintype "passive"))
      (node (ref "MD2") (pin "2") (pinfunction "OUT2A_2") (pintype "bidirectional"))
    )
    (net (code "61") (name "Net-(MD2-OUT2B)") (class "Default")
      (node (ref "M2") (pin "3") (pinfunction "3_3") (pintype "passive"))
      (node (ref "MD2") (pin "5") (pinfunction "OUT2B_5") (pintype "bidirectional"))
    )
    (net (code "62") (name "Net-(MD2-RC1)") (class "Default")
      (node (ref "21CT") (pin "1") (pinfunction "1_1") (pintype "passive"))
      (node (ref "21RT") (pin "2") (pinfunction "2_2") (pintype "passive"))
      (node (ref "MD2") (pin "14") (pinfunction "RC1_14") (pintype "bidirectional"))
    )
    (net (code "63") (name "Net-(MD2-RC2)") (class "Default")
      (node (ref "22CT") (pin "1") (pinfunction "1_1") (pintype "passive"))
      (node (ref "22RT") (pin "2") (pinfunction "2_2") (pintype "passive"))
      (node (ref "MD2") (pin "12") (pinfunction "RC2_12") (pintype "bidirectional"))
    )
    (net (code "64") (name "Net-(MD2-SENSE1)") (class "Default")
      (node (ref "21RC") (pin "1") (pinfunction "1_1") (pintype "passive"))
      (node (ref "21RS") (pin "2") (pinfunction "2_2") (pintype "passive"))
      (node (ref "MD2") (pin "23") (pinfunction "SENSE1_23") (pintype "bidirectional"))
    )
    (net (code "65") (name "Net-(MD2-SENSE2)") (class "Default")
      (node (ref "22RC") (pin "2") (pinfunction "2_2") (pintype "passive"))
      (node (ref "22RS") (pin "2") (pinfunction "2_2") (pintype "passive"))
      (node (ref "MD2") (pin "3") (pinfunction "SENSE2_3") (pintype "bidirectional"))
    )
    (net (code "66") (name "Net-(PWR-PadC)") (class "Default")
      (node (ref "PWR") (pin "C") (pinfunction "C_C") (pintype "passive"))
      (node (ref "R11") (pin "1") (pinfunction "1_1") (pintype "passive"))
    )
    (net (code "67") (name "Net-(T1-B)") (class "Default")
      (node (ref "R23") (pin "2") (pinfunction "2_2") (pintype "passive"))
      (node (ref "T1") (pin "3") (pinfunction "B_3") (pintype "passive"))
    )
    (net (code "68") (name "Net-(T1-C)") (class "Default")
      (node (ref "R24") (pin "1") (pinfunction "1_1") (pintype "passive"))
      (node (ref "T1") (pin "1") (pinfunction "C_1") (pintype "passive"))
    )
    (net (code "69") (name "Net-(T2-B)") (class "Default")
      (node (ref "R25") (pin "2") (pinfunction "2_2") (pintype "passive"))
      (node (ref "T2") (pin "3") (pinfunction "B_3") (pintype "passive"))
    )
    (net (code "70") (name "Net-(T2-C)") (class "Default")
      (node (ref "R26") (pin "1") (pinfunction "1_1") (pintype "passive"))
      (node (ref "T2") (pin "1") (pinfunction "C_1") (pintype "passive"))
    )
    (net (code "71") (name "PGC") (class "Default")
      (node (ref "IC1") (pin "22") (pinfunction "AN3/RP1/CN5/PGC1/RB1_22") (pintype "bidirectional"))
      (node (ref "ICD") (pin "5") (pinfunction "5_5") (pintype "passive"))
    )
    (net (code "72") (name "PGD") (class "Default")
      (node (ref "IC1") (pin "21") (pinfunction "AN2/RP0/CN4/PGD1/RB0_21") (pintype "bidirectional"))
      (node (ref "ICD") (pin "4") (pinfunction "4_4") (pintype "passive"))
    )
    (net (code "73") (name "RFM_CS") (class "Default")
      (node (ref "IC1") (pin "27") (pinfunction "AN12/RP18/CN10/RC2_27") (pintype "bidirectional"))
      (node (ref "MOUTH") (pin "14") (pinfunction "NSEL_14") (pintype "input"))
    )
    (net (code "74") (name "USBD+") (class "Default")
      (node (ref "IC1") (pin "8") (pinfunction "RP10/CN16/PGD2/D+/RB10_8") (pintype "bidirectional"))
      (node (ref "R27") (pin "2") (pinfunction "2_2") (pintype "passive"))
    )
    (net (code "75") (name "USBD-") (class "Default")
      (node (ref "IC1") (pin "9") (pinfunction "PR11/CN15/PGC2/D-/RB11_9") (pintype "bidirectional"))
      (node (ref "R28") (pin "2") (pinfunction "2_2") (pintype "passive"))
    )
    (net (code "76") (name "VBUS") (class "Default")
      (node (ref "F2") (pin "2") (pinfunction "2_2") (pintype "passive"))
      (node (ref "IC1") (pin "42") (pinfunction "CN24/VBUS/RB6_42") (pintype "bidirectional"))
    )
    (net (code "77") (name "VIN") (class "Default")
      (node (ref "1LDB") (pin "1") (pinfunction "1_1") (pintype "passive"))
      (node (ref "1LDC") (pin "+") (pinfunction "+_+") (pintype "passive"))
      (node (ref "2LDB") (pin "1") (pinfunction "1_1") (pintype "passive"))
      (node (ref "2LDC") (pin "+") (pinfunction "+_+") (pintype "passive"))
      (node (ref "C11") (pin "+") (pinfunction "+_+") (pintype "passive"))
      (node (ref "C12") (pin "1") (pinfunction "1_1") (pintype "passive"))
      (node (ref "C13") (pin "1") (pinfunction "1_1") (pintype "passive"))
      (node (ref "D1") (pin "C") (pinfunction "C_C") (pintype "passive"))
      (node (ref "MD1") (pin "24") (pinfunction "VLOAD_24") (pintype "bidirectional"))
      (node (ref "MD2") (pin "24") (pinfunction "VLOAD_24") (pintype "bidirectional"))
      (node (ref "PWR_IN") (pin "8") (pinfunction "8_8") (pintype "passive"))
      (node (ref "VR1") (pin "3") (pinfunction "IN_3") (pintype "input"))
    )
    (net (code "78") (name "unconnected-(CN2-PadID)") (class "Default")
      (node (ref "CN2") (pin "ID") (pinfunction "ID_ID") (pintype "bidirectional"))
    )
    (net (code "79") (name "unconnected-(DIO2-Pad8)") (class "Default")
      (node (ref "DIO2") (pin "8") (pinfunction "8_8") (pintype "passive"))
    )
    (net (code "80") (name "unconnected-(MOUTH-CLK-Pad5)") (class "Default")
      (node (ref "MOUTH") (pin "5") (pinfunction "CLK_5") (pintype "bidirectional"))
    )
    (net (code "81") (name "unconnected-(MOUTH-DCLK-Pad4)") (class "Default")
      (node (ref "MOUTH") (pin "4") (pinfunction "DCLK_4") (pintype "bidirectional"))
    )
    (net (code "82") (name "unconnected-(MOUTH-FSK-Pad3)") (class "Default")
      (node (ref "MOUTH") (pin "3") (pinfunction "FSK_3") (pintype "bidirectional"))
    )
    (net (code "83") (name "unconnected-(MOUTH-NINT-Pad11)") (class "Default")
      (node (ref "MOUTH") (pin "11") (pinfunction "NINT_11") (pintype "bidirectional"))
    )
    (net (code "84") (name "unconnected-(PWR_IN-Pad1)") (class "Default")
      (node (ref "PWR_IN") (pin "1") (pinfunction "1_1") (pintype "passive"))
    )
    (net (code "85") (name "unconnected-(PWR_IN-Pad2)") (class "Default")
      (node (ref "PWR_IN") (pin "2") (pinfunction "2_2") (pintype "passive"))
    )
    (net (code "86") (name "{slash}RST") (class "Default")
      (node (ref "IC1") (pin "18") (pinfunction "~{MCLR}_18") (pintype "bidirectional"))
      (node (ref "ICD") (pin "1") (pinfunction "1_1") (pintype "passive"))
      (node (ref "MOUTH") (pin "6") (pinfunction "/RESET_6") (pintype "bidirectional"))
      (node (ref "PWR_IN") (pin "3") (pinfunction "3_3") (pintype "passive"))
      (node (ref "R21") (pin "2") (pinfunction "2_2") (pintype "passive"))
      (node (ref "S1") (pin "A2") (pinfunction "1_A2") (pintype "passive"))
    )
  )
)
